# ADC-DAC_Converter.net
KiCad netlist of a schematic drawn in Altium Designer
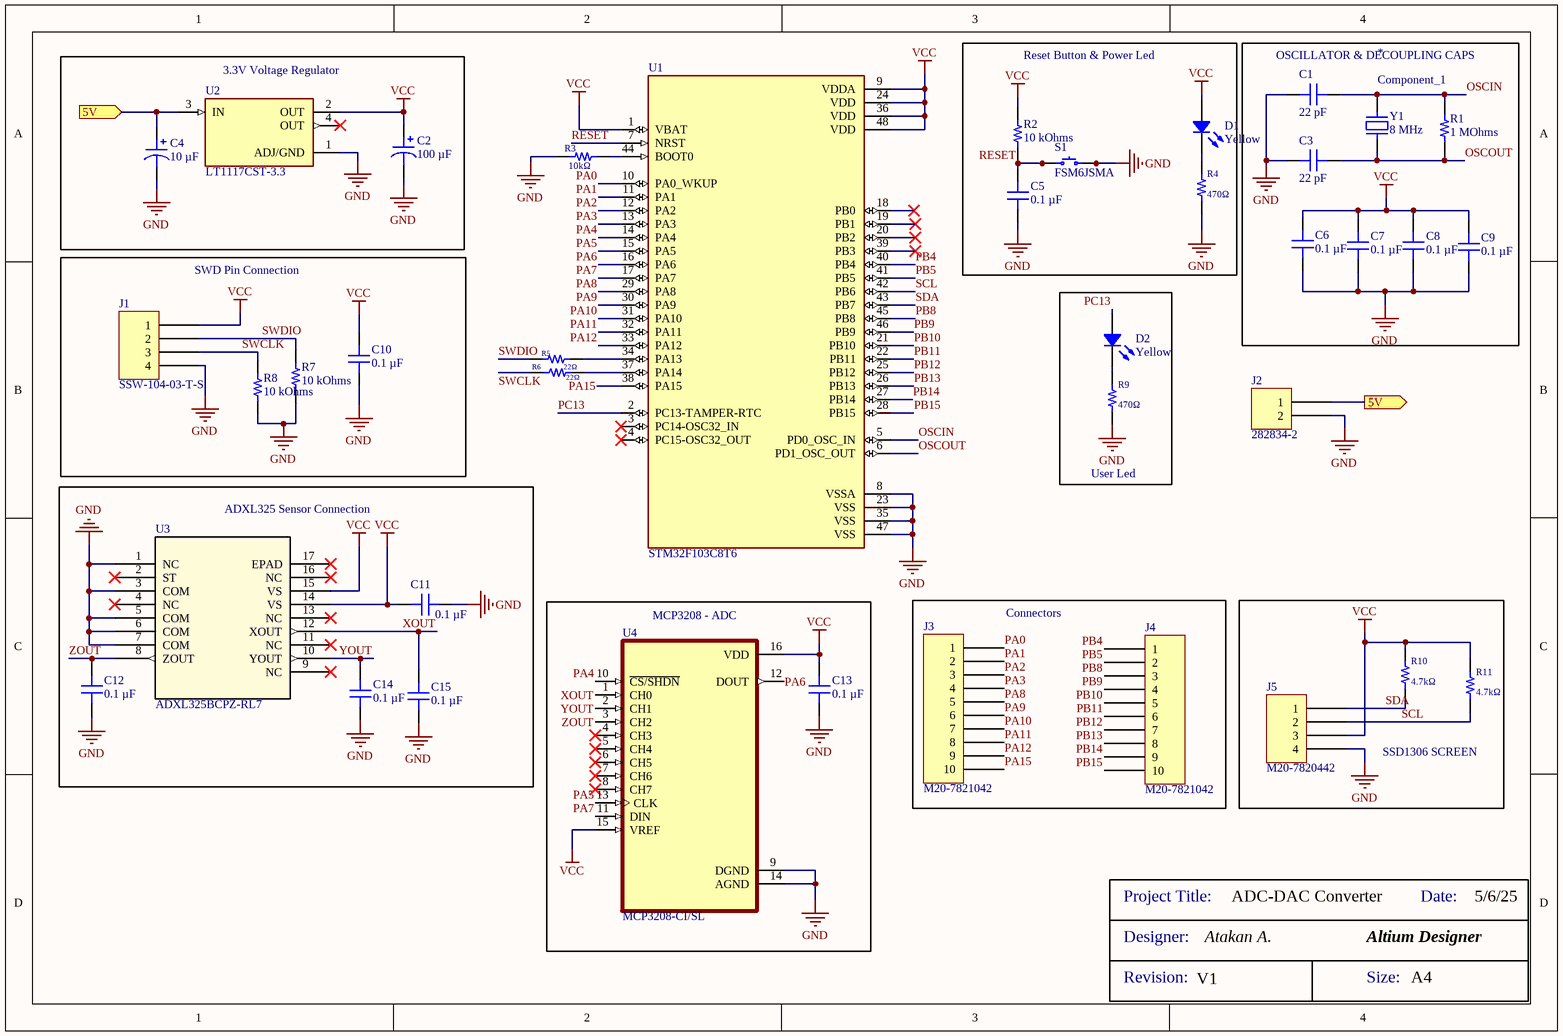
[diagram p0: ADC-DAC Converter.SchDoc]

(export (version "E")
  (design (tool "Eeschema 10.0.6"))
  (components
    (comp (ref "C1")
      (value "22 pF")
      (footprint "CAP 0805_2012")
      (description "CAP CER 22PF 25V C0G/NP0 0805")
      (fields
        (field (name "PART NUMBER") "885012007030")
        (field (name "CAPACITANCE") "22 pF")
        (field (name "MANUFACTURER") "Würth Elektronik")
      )
      (libsource (lib "Lib") (part "Capacitor"))
    )
    (comp (ref "C2")
      (value "100 µF")
      (footprint "CAP POL 1411_3528")
      (description "CAP TANT 100UF 10% 16V 1411")
      (fields (field (name "PART NUMBER") "T491T106K016AT") (field (name "MANUFACTURER") "KEMET"))
      (libsource (lib "Lib") (part "Polarised Capacitor"))
    )
    (comp (ref "C3")
      (value "22 pF")
      (footprint "CAP 0805_2012")
      (description "CAP CER 22PF 25V C0G/NP0 0805")
      (fields (field (name "PART NUMBER") "885012007030") (field (name "MANUFACTURER") "Würth Elektronik"))
      (libsource (lib "Lib") (part "Capacitor"))
    )
    (comp (ref "C4")
      (value "10 µF")
      (footprint "CAP POL 1411_3528")
      (description "CAP TANT 10UF 10% 16V 1411")
      (fields (field (name "PART NUMBER") "T491T106K016AT") (field (name "MANUFACTURER") "KEMET"))
      (libsource (lib "Lib") (part "Polarised Capacitor"))
    )
    (comp (ref "C5")
      (value "0.1 µF")
      (footprint "CAP 1206_3216 - 0.8MM")
      (description "CAP CER 0.1UF 10V X7R 1206")
      (fields (field (name "PART NUMBER") "C1206C104K8RAC7800") (field (name "MANUFACTURER") "KEMET"))
      (libsource (lib "Lib") (part "Capacitor"))
    )
    (comp (ref "C6")
      (value "0.1 µF")
      (footprint "CAP 1206_3216 - 0.8MM")
      (description "CAP CER 0.1UF 10V X7R 1206")
      (fields (field (name "PART NUMBER") "C1206C104K8RAC7800") (field (name "MANUFACTURER") "KEMET"))
      (libsource (lib "Lib") (part "Capacitor"))
    )
    (comp (ref "C7")
      (value "0.1 µF")
      (footprint "CAP 1206_3216 - 0.8MM")
      (description "CAP CER 0.1UF 10V X7R 1206")
      (fields (field (name "PART NUMBER") "C1206C104K8RAC7800") (field (name "MANUFACTURER") "KEMET"))
      (libsource (lib "Lib") (part "Capacitor"))
    )
    (comp (ref "C8")
      (value "0.1 µF")
      (footprint "CAP 1206_3216 - 0.8MM")
      (description "CAP CER 0.1UF 10V X7R 1206")
      (fields (field (name "PART NUMBER") "C1206C104K8RAC7800") (field (name "MANUFACTURER") "KEMET"))
      (libsource (lib "Lib") (part "Capacitor"))
    )
    (comp (ref "C9")
      (value "0.1 µF")
      (footprint "CAP 1206_3216 - 0.8MM")
      (description "CAP CER 0.1UF 10V X7R 1206")
      (fields (field (name "PART NUMBER") "C1206C104K8RAC7800") (field (name "MANUFACTURER") "KEMET"))
      (libsource (lib "Lib") (part "Capacitor"))
    )
    (comp (ref "C10")
      (value "0.1 µF")
      (footprint "CAP 1206_3216 - 0.8MM")
      (description "CAP CER 0.1UF 10V X7R 1206")
      (fields (field (name "PART NUMBER") "C1206C104K8RAC7800") (field (name "MANUFACTURER") "KEMET"))
      (libsource (lib "Lib") (part "Capacitor"))
    )
    (comp (ref "C11")
      (value "0.1 µF")
      (footprint "CAP 0805_2012")
      (description "CAP CER 0.1UF 25V X7R 0805")
      (fields
        (field (name "PART NUMBER") "0805Y0250104KXT")
        (field (name "CAPACITANCE") "0.1 µF")
        (field (name "MANUFACTURER") "Knowles Syfer")
      )
      (libsource (lib "Lib") (part "Capacitor"))
    )
    (comp (ref "C12")
      (value "0.1 µF")
      (footprint "CAP 0805_2012")
      (description "CAP CER 0.1UF 25V X7R 0805")
      (fields
        (field (name "PART NUMBER") "0805Y0250104KXT")
        (field (name "CAPACITANCE") "0.1 µF")
        (field (name "MANUFACTURER") "Knowles Syfer")
      )
      (libsource (lib "Lib") (part "Capacitor"))
    )
    (comp (ref "C13")
      (value "0.1 µF")
      (footprint "CAP 0805_2012")
      (description "CAP CER 0.1UF 25V X7R 0805")
      (fields
        (field (name "PART NUMBER") "0805Y0250104KXT")
        (field (name "CAPACITANCE") "0.1 µF")
        (field (name "MANUFACTURER") "Knowles Syfer")
      )
      (libsource (lib "Lib") (part "Capacitor"))
    )
    (comp (ref "C14")
      (value "0.1 µF")
      (footprint "CAP 0805_2012")
      (description "CAP CER 0.1UF 25V X7R 0805")
      (fields
        (field (name "PART NUMBER") "0805Y0250104KXT")
        (field (name "CAPACITANCE") "0.1 µF")
        (field (name "MANUFACTURER") "Knowles Syfer")
      )
      (libsource (lib "Lib") (part "Capacitor"))
    )
    (comp (ref "C15")
      (value "0.1 µF")
      (footprint "CAP 0805_2012")
      (description "CAP CER 0.1UF 25V X7R 0805")
      (fields
        (field (name "PART NUMBER") "0805Y0250104KXT")
        (field (name "CAPACITANCE") "0.1 µF")
        (field (name "MANUFACTURER") "Knowles Syfer")
      )
      (libsource (lib "Lib") (part "Capacitor"))
    )
    (comp (ref "D1")
      (value "Yellow")
      (footprint "LED 1206_3216 YELLOW")
      (description "LED YELLOW 1206 SMD")
      (fields (field (name "PART NUMBER") "5990240007F") (field (name "MANUFACTURER") "Dialight"))
      (libsource (lib "Lib") (part "LED"))
    )
    (comp (ref "D2")
      (value "Yellow")
      (footprint "LED 1206_3216 YELLOW")
      (description "LED YELLOW 1206 SMD")
      (fields (field (name "PART NUMBER") "5990240007F") (field (name "MANUFACTURER") "Dialight"))
      (libsource (lib "Lib") (part "LED"))
    )
    (comp (ref "J1")
      (value "SSW-104-03-T-S")
      (footprint "SAMTEC SSW-104-03-T-S")
      (description "CONN RCPT 4POS 0.1 TIN PCB")
      (fields (field (name "MANUFACTURER") "Samtec Inc."))
      (libsource (lib "Lib") (part "4 Pin"))
    )
    (comp (ref "J2")
      (value "282834-2")
      (footprint "TE 282834-2")
      (description "TERM BLK 2P SIDE ENT 2.54MM PCB")
      (fields (field (name "MANUFACTURER") "TE Connectivity AMP Connectors") (field (name "VOLTAGE") "150V"))
      (libsource (lib "Lib") (part "2 Pin"))
    )
    (comp (ref "J3")
      (value "M20-7821042")
      (footprint "HARWIN M20-7821045")
      (description "CONN RCPT 10POS 0.1 GOLD PCB")
      (fields (field (name "MANUFACTURER") "Harwin Inc."))
      (libsource (lib "Lib") (part "10 Pin"))
    )
    (comp (ref "J4")
      (value "M20-7821042")
      (footprint "HARWIN M20-7821045")
      (description "CONN RCPT 10POS 0.1 GOLD PCB")
      (fields (field (name "MANUFACTURER") "Harwin Inc."))
      (libsource (lib "") (part "10 Pin_1"))
    )
    (comp (ref "J5")
      (value "M20-7820442")
      (footprint "HARWIN M20-7820445")
      (description "CONN RCPT 4POS 0.1 GOLD PCB")
      (fields (field (name "MANUFACTURER") "Harwin Inc."))
      (libsource (lib "Lib") (part "4 Pin"))
    )
    (comp (ref "R1")
      (value "1 MOhms")
      (footprint "RES 0805_2012")
      (description "RES SMD 1M OHM 1% 1/2W 0805")
      (fields (field (name "PART NUMBER") "RCS08051M00FKEA") (field (name "MANUFACTURER") "Vishay Dale"))
      (libsource (lib "Lib") (part "Resistor"))
    )
    (comp (ref "R2")
      (value "10 kOhms")
      (footprint "RES 1206_3216")
      (description "RES SMD 10K OHM 1% 1/2W 1206")
      (fields (field (name "PART NUMBER") "ESR18EZPF1002") (field (name "MANUFACTURER") "Rohm Semiconductor"))
      (libsource (lib "Lib") (part "Resistor"))
    )
    (comp (ref "R3")
      (value "10kΩ")
      (footprint "RES 0805_2012")
      (description "RES SMD 22 OHM 0.1% 1/10W 0805")
      (fields
        (field (name "PART NUMBER") "CPF0805B22RE1")
        (field (name "MANUFACTURER") "TE Connectivity Passive Product")
      )
      (libsource (lib "Lib") (part "Resistor"))
    )
    (comp (ref "R4")
      (value "470Ω")
      (footprint "RES 0805_2012")
      (description "RES SMD 22 OHM 0.1% 1/10W 0805")
      (fields
        (field (name "PART NUMBER") "CPF0805B22RE1")
        (field (name "MANUFACTURER") "TE Connectivity Passive Product")
      )
      (libsource (lib "Lib") (part "Resistor"))
    )
    (comp (ref "R5")
      (value "22Ω")
      (footprint "RES 0805_2012")
      (description "RES SMD 22 OHM 0.1% 1/10W 0805")
      (fields
        (field (name "PART NUMBER") "CPF0805B22RE1")
        (field (name "MANUFACTURER") "TE Connectivity Passive Product")
      )
      (libsource (lib "Lib") (part "Resistor"))
    )
    (comp (ref "R6")
      (value "22Ω")
      (footprint "RES 0805_2012")
      (description "RES SMD 22 OHM 0.1% 1/10W 0805")
      (fields
        (field (name "PART NUMBER") "CPF0805B22RE1")
        (field (name "MANUFACTURER") "TE Connectivity Passive Product")
      )
      (libsource (lib "Lib") (part "Resistor"))
    )
    (comp (ref "R7")
      (value "10 kOhms")
      (footprint "RES 1206_3216")
      (description "RES SMD 10K OHM 1% 1/2W 1206")
      (fields (field (name "PART NUMBER") "ESR18EZPF1002") (field (name "MANUFACTURER") "Rohm Semiconductor"))
      (libsource (lib "Lib") (part "Resistor"))
    )
    (comp (ref "R8")
      (value "10 kOhms")
      (footprint "RES 1206_3216")
      (description "RES SMD 10K OHM 1% 1/2W 1206")
      (fields (field (name "PART NUMBER") "ESR18EZPF1002") (field (name "MANUFACTURER") "Rohm Semiconductor"))
      (libsource (lib "Lib") (part "Resistor"))
    )
    (comp (ref "R9")
      (value "470Ω")
      (footprint "RES 0805_2012")
      (description "RES SMD 22 OHM 0.1% 1/10W 0805")
      (fields
        (field (name "PART NUMBER") "CPF0805B22RE1")
        (field (name "MANUFACTURER") "TE Connectivity Passive Product")
      )
      (libsource (lib "Lib") (part "Resistor"))
    )
    (comp (ref "R10")
      (value "4.7kΩ")
      (footprint "RES 0805_2012")
      (description "RES SMD 22 OHM 0.1% 1/10W 0805")
      (fields
        (field (name "PART NUMBER") "CPF0805B22RE1")
        (field (name "MANUFACTURER") "TE Connectivity Passive Product")
      )
      (libsource (lib "Lib") (part "Resistor"))
    )
    (comp (ref "R11")
      (value "4.7kΩ")
      (footprint "RES 0805_2012")
      (description "RES SMD 22 OHM 0.1% 1/10W 0805")
      (fields
        (field (name "PART NUMBER") "CPF0805B22RE1")
        (field (name "MANUFACTURER") "TE Connectivity Passive Product")
      )
      (libsource (lib "Lib") (part "Resistor"))
    )
    (comp (ref "S1")
      (value "FSM6JSMA")
      (footprint "TE FSM6JSMA")
      (description "SWITCH TACTILE SPST-NO 0.05A 24V")
      (fields (field (name "MANUFACTURER") "TE Connectivity ALCOSWITCH Switches"))
      (libsource (lib "Lib") (part "SPST-NO 4 PIN"))
    )
    (comp (ref "U1")
      (value "STM32F103C8T6")
      (footprint "QFP50P900X900X160-48N")
      (description "ARM® Cortex®-M3 STM32F1 Microcontroller IC 32-Bit 72MHz 64KB (64K x 8) FLASH 48-LQFP (7x7)")
      (fields (field (name "MF") "STMicroelectronics"))
      (libsource (lib "STM32F103C8T6") (part "STM32F103C8T6"))
    )
    (comp (ref "U2")
      (value "LT1117CST-3.3")
      (footprint "REG_LT1117CST-3.3")
      (description "Linear Voltage Regulator IC Positive Fixed 1 Output 800mA SOT-223-3")
      (fields (field (name "MF") "Analog Devices / Linear Technology"))
      (libsource (lib "LT1117CST-3.3") (part "LT1117CST-3.3"))
    )
    (comp (ref "U3")
      (value "ADXL325BCPZ-RL7")
      (footprint "CP_16_5A_ADI-M")
      (description "No Description Available")
      (libsource (lib "ADXL325BCPZ-RL7") (part "ADXL325BCPZ-RL7"))
    )
    (comp (ref "U4")
      (value "MCP3208-CI/SL")
      (footprint "SOIC127P600X175-16N")
      (fields (field (name "MF") "Microchip Technology"))
      (libsource (lib "MCP3208-CI_SL") (part "MCP3208-CI/SL"))
    )
    (comp (ref "Y1")
      (value "8 MHz")
      (footprint "ABRACON ABLS")
      (description "CRYSTAL 8.0000MHZ 16PF SMD")
      (fields
        (field (name "PART NUMBER") "ABLS-8.000MHZ-16-A-4-H-T")
        (field (name "MANUFACTURER") "Abracon LLC")
      )
      (libsource (lib "Lib") (part "Abracon Crystal ABLS"))
    )
  )
  (nets
    (net (code "1") (name "/5V") (class "Default")
      (node (ref "C4") (pin "1") (pinfunction "1_1") (pintype "passive"))
      (node (ref "J2") (pin "1") (pinfunction "1_1") (pintype "passive"))
      (node (ref "U2") (pin "3") (pinfunction "IN_3") (pintype "input"))
    )
    (net (code "2") (name "/OSCIN") (class "Default")
      (node (ref "C1") (pin "2") (pinfunction "2_2") (pintype "passive"))
      (node (ref "R1") (pin "2") (pinfunction "2_2") (pintype "passive"))
      (node (ref "U1") (pin "5") (pinfunction "PD0_OSC_IN_5") (pintype "bidirectional"))
      (node (ref "Y1") (pin "2") (pinfunction "2_2") (pintype "passive"))
    )
    (net (code "3") (name "/OSCOUT") (class "Default")
      (node (ref "C3") (pin "2") (pinfunction "2_2") (pintype "passive"))
      (node (ref "R1") (pin "1") (pinfunction "1_1") (pintype "passive"))
      (node (ref "U1") (pin "6") (pinfunction "PD1_OSC_OUT_6") (pintype "bidirectional"))
      (node (ref "Y1") (pin "1") (pinfunction "1_1") (pintype "passive"))
    )
    (net (code "4") (name "/PA0") (class "Default")
      (node (ref "J3") (pin "1") (pinfunction "1_1") (pintype "passive"))
      (node (ref "U1") (pin "10") (pinfunction "PA0_WKUP_10") (pintype "bidirectional"))
    )
    (net (code "5") (name "/PA1") (class "Default")
      (node (ref "J3") (pin "2") (pinfunction "2_2") (pintype "passive"))
      (node (ref "U1") (pin "11") (pinfunction "PA1_11") (pintype "bidirectional"))
    )
    (net (code "6") (name "/PA2") (class "Default")
      (node (ref "J3") (pin "3") (pinfunction "3_3") (pintype "passive"))
      (node (ref "U1") (pin "12") (pinfunction "PA2_12") (pintype "bidirectional"))
    )
    (net (code "7") (name "/PA3") (class "Default")
      (node (ref "J3") (pin "4") (pinfunction "4_4") (pintype "passive"))
      (node (ref "U1") (pin "13") (pinfunction "PA3_13") (pintype "bidirectional"))
    )
    (net (code "8") (name "/PA4") (class "Default")
      (node (ref "U1") (pin "14") (pinfunction "PA4_14") (pintype "bidirectional"))
      (node (ref "U4") (pin "10") (pinfunction "~{CS/SHDN}_10") (pintype "input"))
    )
    (net (code "9") (name "/PA5") (class "Default")
      (node (ref "U1") (pin "15") (pinfunction "PA5_15") (pintype "bidirectional"))
      (node (ref "U4") (pin "13") (pinfunction "CLK_13") (pintype "input"))
    )
    (net (code "10") (name "/PA6") (class "Default")
      (node (ref "U1") (pin "16") (pinfunction "PA6_16") (pintype "bidirectional"))
      (node (ref "U4") (pin "12") (pinfunction "DOUT_12") (pintype "output"))
    )
    (net (code "11") (name "/PA7") (class "Default")
      (node (ref "U1") (pin "17") (pinfunction "PA7_17") (pintype "bidirectional"))
      (node (ref "U4") (pin "11") (pinfunction "DIN_11") (pintype "input"))
    )
    (net (code "12") (name "/PA8") (class "Default")
      (node (ref "J3") (pin "5") (pinfunction "5_5") (pintype "passive"))
      (node (ref "U1") (pin "29") (pinfunction "PA8_29") (pintype "bidirectional"))
    )
    (net (code "13") (name "/PA9") (class "Default")
      (node (ref "J3") (pin "6") (pinfunction "6_6") (pintype "passive"))
      (node (ref "U1") (pin "30") (pinfunction "PA9_30") (pintype "bidirectional"))
    )
    (net (code "14") (name "/PA10") (class "Default")
      (node (ref "J3") (pin "7") (pinfunction "7_7") (pintype "passive"))
      (node (ref "U1") (pin "31") (pinfunction "PA10_31") (pintype "bidirectional"))
    )
    (net (code "15") (name "/PA11") (class "Default")
      (node (ref "J3") (pin "8") (pinfunction "8_8") (pintype "passive"))
      (node (ref "U1") (pin "32") (pinfunction "PA11_32") (pintype "bidirectional"))
    )
    (net (code "16") (name "/PA12") (class "Default")
      (node (ref "J3") (pin "9") (pinfunction "9_9") (pintype "passive"))
      (node (ref "U1") (pin "33") (pinfunction "PA12_33") (pintype "bidirectional"))
    )
    (net (code "17") (name "/PA15") (class "Default")
      (node (ref "J3") (pin "10") (pinfunction "10_10") (pintype "passive"))
      (node (ref "U1") (pin "38") (pinfunction "PA15_38") (pintype "bidirectional"))
    )
    (net (code "18") (name "/PB4") (class "Default")
      (node (ref "J4") (pin "1") (pinfunction "1_1") (pintype "passive"))
      (node (ref "U1") (pin "40") (pinfunction "PB4_40") (pintype "bidirectional"))
    )
    (net (code "19") (name "/PB5") (class "Default")
      (node (ref "J4") (pin "2") (pinfunction "2_2") (pintype "passive"))
      (node (ref "U1") (pin "41") (pinfunction "PB5_41") (pintype "bidirectional"))
    )
    (net (code "20") (name "/PB8") (class "Default")
      (node (ref "J4") (pin "3") (pinfunction "3_3") (pintype "passive"))
      (node (ref "U1") (pin "45") (pinfunction "PB8_45") (pintype "bidirectional"))
    )
    (net (code "21") (name "/PB9") (class "Default")
      (node (ref "J4") (pin "4") (pinfunction "4_4") (pintype "passive"))
      (node (ref "U1") (pin "46") (pinfunction "PB9_46") (pintype "bidirectional"))
    )
    (net (code "22") (name "/PB10") (class "Default")
      (node (ref "J4") (pin "5") (pinfunction "5_5") (pintype "passive"))
      (node (ref "U1") (pin "21") (pinfunction "PB10_21") (pintype "bidirectional"))
    )
    (net (code "23") (name "/PB11") (class "Default")
      (node (ref "J4") (pin "6") (pinfunction "6_6") (pintype "passive"))
      (node (ref "U1") (pin "22") (pinfunction "PB11_22") (pintype "bidirectional"))
    )
    (net (code "24") (name "/PB12") (class "Default")
      (node (ref "J4") (pin "7") (pinfunction "7_7") (pintype "passive"))
      (node (ref "U1") (pin "25") (pinfunction "PB12_25") (pintype "bidirectional"))
    )
    (net (code "25") (name "/PB13") (class "Default")
      (node (ref "J4") (pin "8") (pinfunction "8_8") (pintype "passive"))
      (node (ref "U1") (pin "26") (pinfunction "PB13_26") (pintype "bidirectional"))
    )
    (net (code "26") (name "/PB14") (class "Default")
      (node (ref "J4") (pin "9") (pinfunction "9_9") (pintype "passive"))
      (node (ref "U1") (pin "27") (pinfunction "PB14_27") (pintype "bidirectional"))
    )
    (net (code "27") (name "/PB15") (class "Default")
      (node (ref "J4") (pin "10") (pinfunction "10_10") (pintype "passive"))
      (node (ref "U1") (pin "28") (pinfunction "PB15_28") (pintype "bidirectional"))
    )
    (net (code "28") (name "/PC13") (class "Default")
      (node (ref "D2") (pin "1") (pinfunction "1_1") (pintype "passive"))
      (node (ref "U1") (pin "2") (pinfunction "PC13-TAMPER-RTC_2") (pintype "bidirectional"))
    )
    (net (code "29") (name "/RESET") (class "Default")
      (node (ref "C5") (pin "2") (pinfunction "2_2") (pintype "passive"))
      (node (ref "R2") (pin "1") (pinfunction "1_1") (pintype "passive"))
      (node (ref "S1") (pin "1") (pinfunction "1_1") (pintype "passive"))
      (node (ref "S1") (pin "2") (pinfunction "2_2") (pintype "passive"))
      (node (ref "U1") (pin "7") (pinfunction "NRST_7") (pintype "input"))
    )
    (net (code "30") (name "/SCL") (class "Default")
      (node (ref "J5") (pin "2") (pinfunction "2_2") (pintype "passive"))
      (node (ref "R11") (pin "2") (pinfunction "2_2") (pintype "passive"))
      (node (ref "U1") (pin "42") (pinfunction "PB6_42") (pintype "bidirectional"))
    )
    (net (code "31") (name "/SDA") (class "Default")
      (node (ref "J5") (pin "1") (pinfunction "1_1") (pintype "passive"))
      (node (ref "R10") (pin "2") (pinfunction "2_2") (pintype "passive"))
      (node (ref "U1") (pin "43") (pinfunction "PB7_43") (pintype "bidirectional"))
    )
    (net (code "32") (name "/SWCLK") (class "Default")
      (node (ref "J1") (pin "3") (pinfunction "3_3") (pintype "passive"))
      (node (ref "R6") (pin "2") (pinfunction "2_2") (pintype "passive"))
      (node (ref "R8") (pin "2") (pinfunction "2_2") (pintype "passive"))
    )
    (net (code "33") (name "/SWDIO") (class "Default")
      (node (ref "J1") (pin "2") (pinfunction "2_2") (pintype "passive"))
      (node (ref "R5") (pin "2") (pinfunction "2_2") (pintype "passive"))
      (node (ref "R7") (pin "2") (pinfunction "2_2") (pintype "passive"))
    )
    (net (code "34") (name "/XOUT") (class "Default")
      (node (ref "C15") (pin "2") (pinfunction "2_2") (pintype "passive"))
      (node (ref "U3") (pin "12") (pinfunction "XOUT_12") (pintype "output"))
      (node (ref "U4") (pin "1") (pinfunction "CH0_1") (pintype "input"))
    )
    (net (code "35") (name "/YOUT") (class "Default")
      (node (ref "C14") (pin "2") (pinfunction "2_2") (pintype "passive"))
      (node (ref "U3") (pin "10") (pinfunction "YOUT_10") (pintype "output"))
      (node (ref "U4") (pin "2") (pinfunction "CH1_2") (pintype "input"))
    )
    (net (code "36") (name "/ZOUT") (class "Default")
      (node (ref "C12") (pin "2") (pinfunction "2_2") (pintype "passive"))
      (node (ref "U3") (pin "8") (pinfunction "ZOUT_8") (pintype "output"))
      (node (ref "U4") (pin "3") (pinfunction "CH2_3") (pintype "input"))
    )
    (net (code "37") (name "GND") (class "Default")
      (node (ref "C1") (pin "1") (pinfunction "1_1") (pintype "passive"))
      (node (ref "C10") (pin "1") (pinfunction "1_1") (pintype "passive"))
      (node (ref "C11") (pin "1") (pinfunction "1_1") (pintype "passive"))
      (node (ref "C12") (pin "1") (pinfunction "1_1") (pintype "passive"))
      (node (ref "C13") (pin "1") (pinfunction "1_1") (pintype "passive"))
      (node (ref "C14") (pin "1") (pinfunction "1_1") (pintype "passive"))
      (node (ref "C15") (pin "1") (pinfunction "1_1") (pintype "passive"))
      (node (ref "C2") (pin "2") (pinfunction "2_2") (pintype "passive"))
      (node (ref "C3") (pin "1") (pinfunction "1_1") (pintype "passive"))
      (node (ref "C4") (pin "2") (pinfunction "2_2") (pintype "passive"))
      (node (ref "C5") (pin "1") (pinfunction "1_1") (pintype "passive"))
      (node (ref "C6") (pin "1") (pinfunction "1_1") (pintype "passive"))
      (node (ref "C7") (pin "1") (pinfunction "1_1") (pintype "passive"))
      (node (ref "C8") (pin "1") (pinfunction "1_1") (pintype "passive"))
      (node (ref "C9") (pin "1") (pinfunction "1_1") (pintype "passive"))
      (node (ref "J1") (pin "4") (pinfunction "4_4") (pintype "passive"))
      (node (ref "J2") (pin "2") (pinfunction "2_2") (pintype "passive"))
      (node (ref "J5") (pin "4") (pinfunction "4_4") (pintype "passive"))
      (node (ref "R3") (pin "1") (pinfunction "1_1") (pintype "passive"))
      (node (ref "R4") (pin "2") (pinfunction "2_2") (pintype "passive"))
      (node (ref "R7") (pin "1") (pinfunction "1_1") (pintype "passive"))
      (node (ref "R8") (pin "1") (pinfunction "1_1") (pintype "passive"))
      (node (ref "R9") (pin "2") (pinfunction "2_2") (pintype "passive"))
      (node (ref "S1") (pin "3") (pinfunction "3_3") (pintype "passive"))
      (node (ref "S1") (pin "4") (pinfunction "4_4") (pintype "passive"))
      (node (ref "U1") (pin "23") (pinfunction "VSS_23") (pintype "power_in"))
      (node (ref "U1") (pin "35") (pinfunction "VSS_35") (pintype "power_in"))
      (node (ref "U1") (pin "47") (pinfunction "VSS_47") (pintype "power_in"))
      (node (ref "U1") (pin "8") (pinfunction "VSSA_8") (pintype "power_in"))
      (node (ref "U2") (pin "1") (pinfunction "ADJ/GND_1") (pintype "power_in"))
      (node (ref "U3") (pin "1") (pinfunction "NC_1") (pintype "passive"))
      (node (ref "U3") (pin "3") (pinfunction "COM_3") (pintype "passive"))
      (node (ref "U3") (pin "5") (pinfunction "COM_5") (pintype "passive"))
      (node (ref "U3") (pin "6") (pinfunction "COM_6") (pintype "passive"))
      (node (ref "U3") (pin "7") (pinfunction "COM_7") (pintype "passive"))
      (node (ref "U4") (pin "14") (pinfunction "AGND_14") (pintype "power_in"))
      (node (ref "U4") (pin "9") (pinfunction "DGND_9") (pintype "power_in"))
    )
    (net (code "38") (name "Net-(D1-Pad2)") (class "Default")
      (node (ref "D1") (pin "2") (pinfunction "2_2") (pintype "passive"))
      (node (ref "R4") (pin "1") (pinfunction "1_1") (pintype "passive"))
    )
    (net (code "39") (name "Net-(D2-Pad2)") (class "Default")
      (node (ref "D2") (pin "2") (pinfunction "2_2") (pintype "passive"))
      (node (ref "R9") (pin "1") (pinfunction "1_1") (pintype "passive"))
    )
    (net (code "40") (name "Net-(U1-BOOT0)") (class "Default")
      (node (ref "R3") (pin "2") (pinfunction "2_2") (pintype "passive"))
      (node (ref "U1") (pin "44") (pinfunction "BOOT0_44") (pintype "input"))
    )
    (net (code "41") (name "Net-(U1-PA13)") (class "Default")
      (node (ref "R5") (pin "1") (pinfunction "1_1") (pintype "passive"))
      (node (ref "U1") (pin "34") (pinfunction "PA13_34") (pintype "bidirectional"))
    )
    (net (code "42") (name "Net-(U1-PA14)") (class "Default")
      (node (ref "R6") (pin "1") (pinfunction "1_1") (pintype "passive"))
      (node (ref "U1") (pin "37") (pinfunction "PA14_37") (pintype "bidirectional"))
    )
    (net (code "43") (name "VCC") (class "Default")
      (node (ref "C10") (pin "2") (pinfunction "2_2") (pintype "passive"))
      (node (ref "C11") (pin "2") (pinfunction "2_2") (pintype "passive"))
      (node (ref "C13") (pin "2") (pinfunction "2_2") (pintype "passive"))
      (node (ref "C2") (pin "1") (pinfunction "1_1") (pintype "passive"))
      (node (ref "C6") (pin "2") (pinfunction "2_2") (pintype "passive"))
      (node (ref "C7") (pin "2") (pinfunction "2_2") (pintype "passive"))
      (node (ref "C8") (pin "2") (pinfunction "2_2") (pintype "passive"))
      (node (ref "C9") (pin "2") (pinfunction "2_2") (pintype "passive"))
      (node (ref "D1") (pin "1") (pinfunction "1_1") (pintype "passive"))
      (node (ref "J1") (pin "1") (pinfunction "1_1") (pintype "passive"))
      (node (ref "J5") (pin "3") (pinfunction "3_3") (pintype "passive"))
      (node (ref "R10") (pin "1") (pinfunction "1_1") (pintype "passive"))
      (node (ref "R11") (pin "1") (pinfunction "1_1") (pintype "passive"))
      (node (ref "R2") (pin "2") (pinfunction "2_2") (pintype "passive"))
      (node (ref "U1") (pin "1") (pinfunction "VBAT_1") (pintype "bidirectional"))
      (node (ref "U1") (pin "24") (pinfunction "VDD_24") (pintype "power_in"))
      (node (ref "U1") (pin "36") (pinfunction "VDD_36") (pintype "power_in"))
      (node (ref "U1") (pin "48") (pinfunction "VDD_48") (pintype "power_in"))
      (node (ref "U1") (pin "9") (pinfunction "VDDA_9") (pintype "power_in"))
      (node (ref "U2") (pin "2") (pinfunction "OUT_2") (pintype "passive"))
      (node (ref "U3") (pin "14") (pinfunction "VS_14") (pintype "passive"))
      (node (ref "U3") (pin "15") (pinfunction "VS_15") (pintype "passive"))
      (node (ref "U4") (pin "15") (pinfunction "VREF_15") (pintype "input"))
      (node (ref "U4") (pin "16") (pinfunction "VDD_16") (pintype "power_in"))
    )
    (net (code "44") (name "unconnected-(U1-PB0-Pad18)") (class "Default")
      (node (ref "U1") (pin "18") (pinfunction "PB0_18") (pintype "bidirectional+no_connect"))
    )
    (net (code "45") (name "unconnected-(U1-PB1-Pad19)") (class "Default")
      (node (ref "U1") (pin "19") (pinfunction "PB1_19") (pintype "bidirectional+no_connect"))
    )
    (net (code "46") (name "unconnected-(U1-PB2-Pad20)") (class "Default")
      (node (ref "U1") (pin "20") (pinfunction "PB2_20") (pintype "bidirectional+no_connect"))
    )
    (net (code "47") (name "unconnected-(U1-PB3-Pad39)") (class "Default")
      (node (ref "U1") (pin "39") (pinfunction "PB3_39") (pintype "bidirectional+no_connect"))
    )
    (net (code "48") (name "unconnected-(U1-PC14-OSC32_IN-Pad3)") (class "Default")
      (node (ref "U1") (pin "3") (pinfunction "PC14-OSC32_IN_3") (pintype "bidirectional+no_connect"))
    )
    (net (code "49") (name "unconnected-(U1-PC15-OSC32_OUT-Pad4)") (class "Default")
      (node (ref "U1") (pin "4") (pinfunction "PC15-OSC32_OUT_4") (pintype "bidirectional+no_connect"))
    )
    (net (code "50") (name "unconnected-(U2-OUT-Pad4)") (class "Default")
      (node (ref "U2") (pin "4") (pinfunction "OUT_4") (pintype "output+no_connect"))
    )
    (net (code "51") (name "unconnected-(U3-EPAD-Pad17)") (class "Default")
      (node (ref "U3") (pin "17") (pinfunction "EPAD_17") (pintype "passive+no_connect"))
    )
    (net (code "52") (name "unconnected-(U3-NC-Pad4)") (class "Default")
      (node (ref "U3") (pin "4") (pinfunction "NC_4") (pintype "passive+no_connect"))
    )
    (net (code "53") (name "unconnected-(U3-NC-Pad9)") (class "Default")
      (node (ref "U3") (pin "9") (pinfunction "NC_9") (pintype "passive+no_connect"))
    )
    (net (code "54") (name "unconnected-(U3-NC-Pad11)") (class "Default")
      (node (ref "U3") (pin "11") (pinfunction "NC_11") (pintype "passive+no_connect"))
    )
    (net (code "55") (name "unconnected-(U3-NC-Pad13)") (class "Default")
      (node (ref "U3") (pin "13") (pinfunction "NC_13") (pintype "passive+no_connect"))
    )
    (net (code "56") (name "unconnected-(U3-NC-Pad16)") (class "Default")
      (node (ref "U3") (pin "16") (pinfunction "NC_16") (pintype "passive+no_connect"))
    )
    (net (code "57") (name "unconnected-(U3-ST-Pad2)") (class "Default")
      (node (ref "U3") (pin "2") (pinfunction "ST_2") (pintype "passive+no_connect"))
    )
    (net (code "58") (name "unconnected-(U4-CH3-Pad4)") (class "Default")
      (node (ref "U4") (pin "4") (pinfunction "CH3_4") (pintype "input+no_connect"))
    )
    (net (code "59") (name "unconnected-(U4-CH4-Pad5)") (class "Default")
      (node (ref "U4") (pin "5") (pinfunction "CH4_5") (pintype "input+no_connect"))
    )
    (net (code "60") (name "unconnected-(U4-CH5-Pad6)") (class "Default")
      (node (ref "U4") (pin "6") (pinfunction "CH5_6") (pintype "input+no_connect"))
    )
    (net (code "61") (name "unconnected-(U4-CH6-Pad7)") (class "Default")
      (node (ref "U4") (pin "7") (pinfunction "CH6_7") (pintype "input+no_connect"))
    )
    (net (code "62") (name "unconnected-(U4-CH7-Pad8)") (class "Default")
      (node (ref "U4") (pin "8") (pinfunction "CH7_8") (pintype "input+no_connect"))
    )
  )
)
